# tinySensor.net
KiCad netlist of a schematic drawn in EAGLE
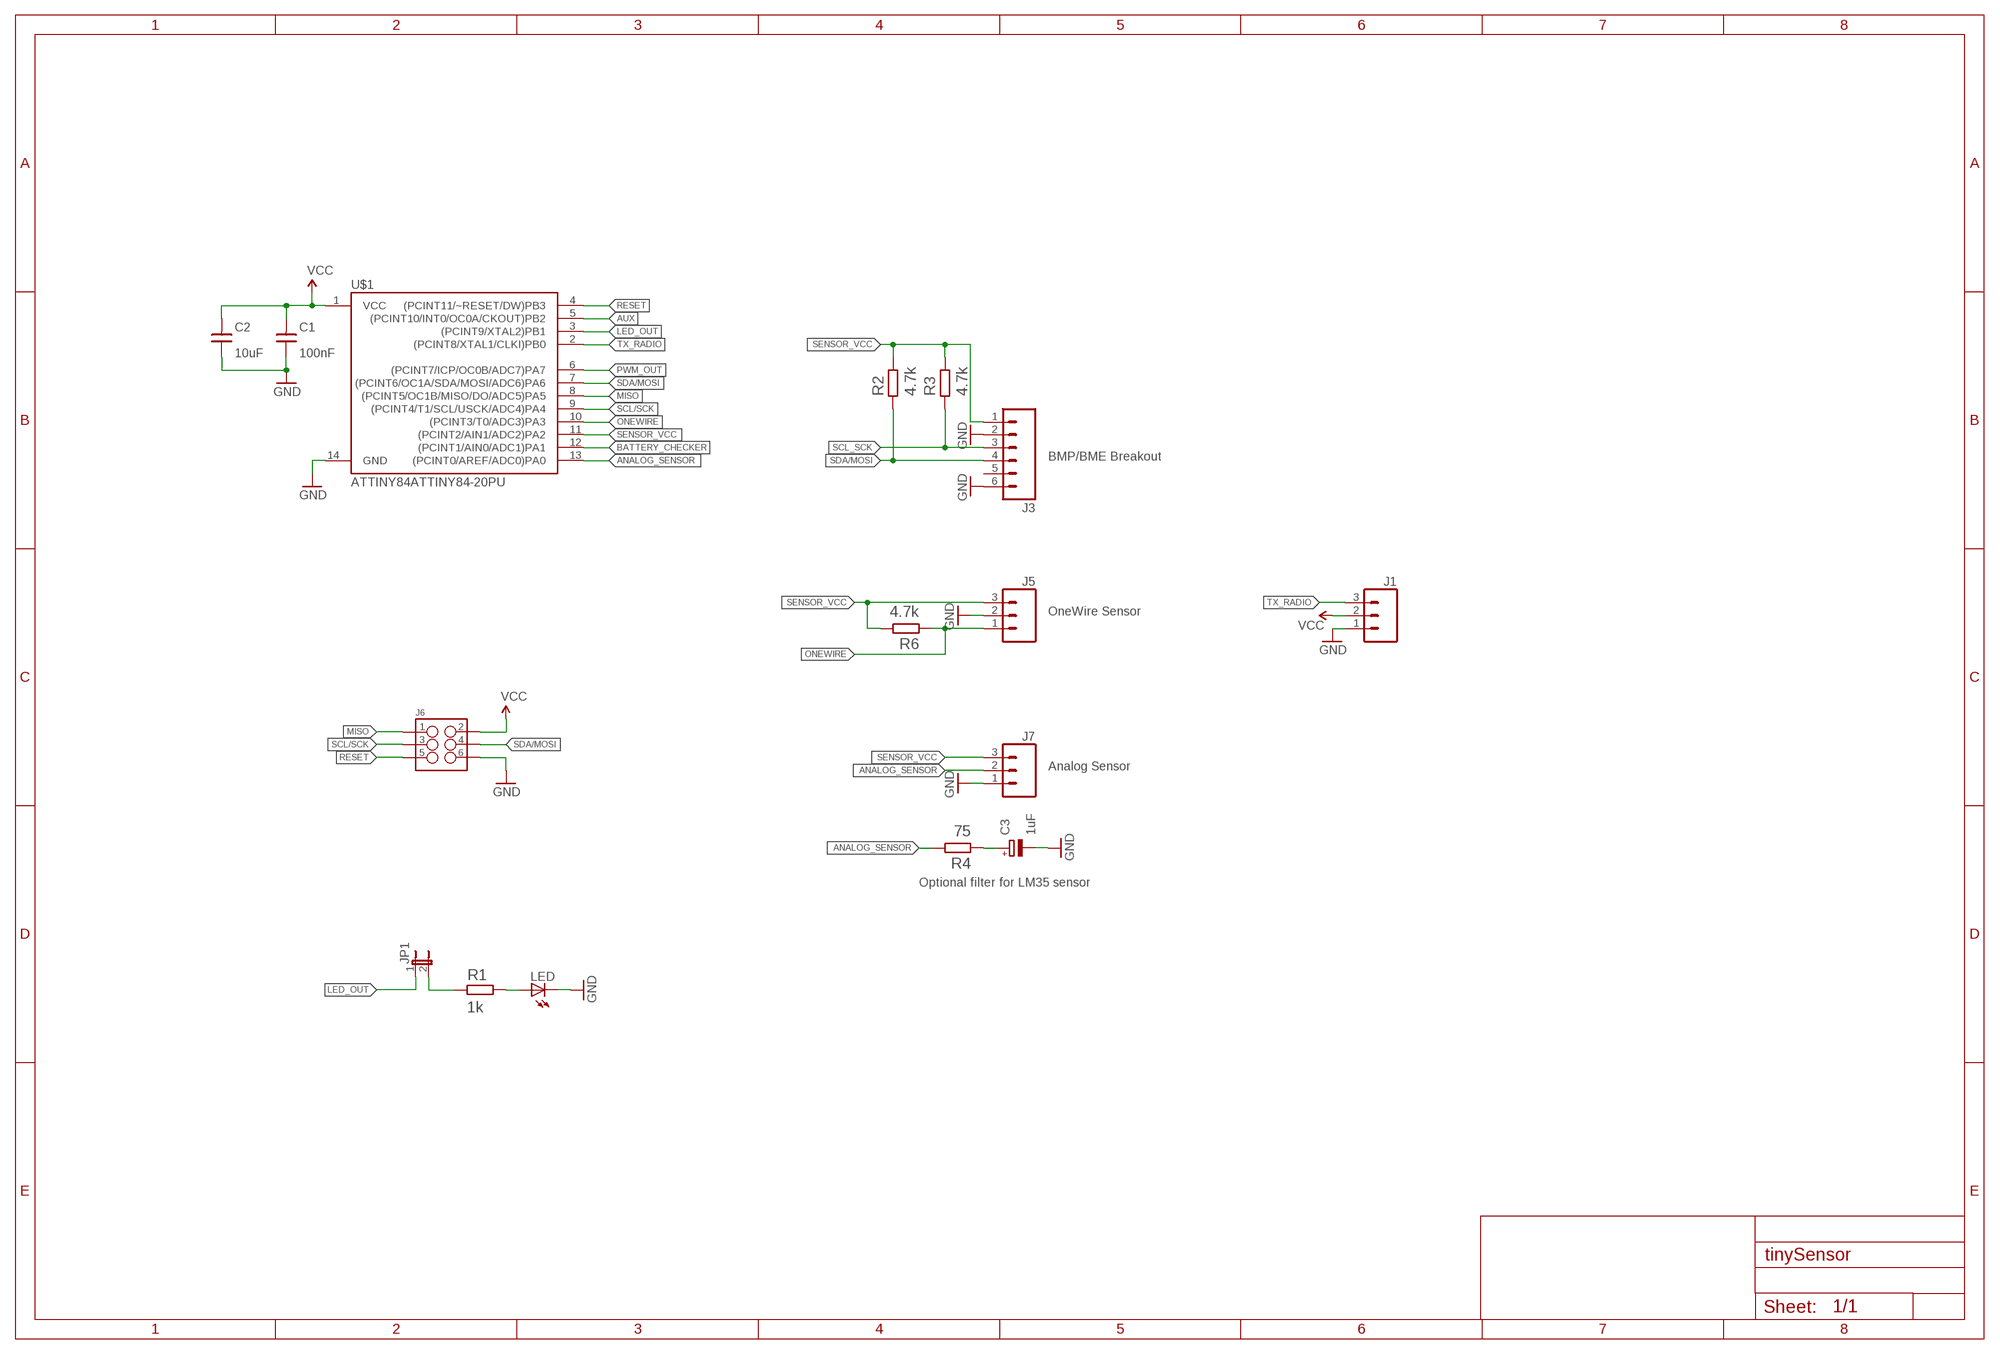
[diagram p0: schematic, sheet 1]

(export (version "E")
  (design (tool "Eeschema 10.0.6"))
  (components
    (comp (ref "C1")
      (value "100nF")
      (footprint "eagle-import:R0805")
      (libsource (lib "eagle-import") (part "C0805"))
    )
    (comp (ref "C2")
      (value "10uF")
      (footprint "eagle-import:R0805")
      (libsource (lib "eagle-import") (part "C0805"))
    )
    (comp (ref "C3")
      (value "1uF")
      (footprint "eagle-import:PANASONIC_C")
      (libsource (lib "eagle-import") (part "CPOL-EUC"))
    )
    (comp (ref "J1")
      (value "M03PTH")
      (footprint "eagle-import:1X03")
      (libsource (lib "eagle-import") (part "M03PTH"))
    )
    (comp (ref "J3")
      (value "M06SIP")
      (footprint "eagle-import:1X06")
      (libsource (lib "eagle-import") (part "M06SIP"))
    )
    (comp (ref "J5")
      (value "M03PTH")
      (footprint "eagle-import:1X03")
      (libsource (lib "eagle-import") (part "M03PTH"))
    )
    (comp (ref "J6")
      (value "M03X2SHROUD")
      (footprint "eagle-import:2X3-SHROUDED")
      (libsource (lib "eagle-import") (part "M03X2SHROUD"))
    )
    (comp (ref "J7")
      (value "M03PTH")
      (footprint "eagle-import:1X03")
      (libsource (lib "eagle-import") (part "M03PTH"))
    )
    (comp (ref "JP1")
      (value "JUMPER-2PTH")
      (footprint "eagle-import:1X02")
      (libsource (lib "eagle-import") (part "JUMPER-2PTH"))
    )
    (comp (ref "LED")
      (value "LED3MM")
      (footprint "eagle-import:LED3MM")
      (libsource (lib "eagle-import") (part "LED3MM"))
    )
    (comp (ref "R1")
      (value "1k")
      (footprint "eagle-import:R0805")
      (libsource (lib "eagle-import") (part "R0805"))
    )
    (comp (ref "R2")
      (value "4.7k")
      (footprint "eagle-import:R0805")
      (libsource (lib "eagle-import") (part "R0805"))
    )
    (comp (ref "R3")
      (value "4.7k")
      (footprint "eagle-import:R0805")
      (libsource (lib "eagle-import") (part "R0805"))
    )
    (comp (ref "R4")
      (value "75")
      (footprint "eagle-import:R0805")
      (libsource (lib "eagle-import") (part "R0805"))
    )
    (comp (ref "R6")
      (value "4.7k")
      (footprint "eagle-import:R0805")
      (libsource (lib "eagle-import") (part "R0805"))
    )
    (comp (ref "U$1")
      (value "ATTINY84ATTINY84-20PU")
      (footprint "eagle-import:DIL14")
      (libsource (lib "eagle-import") (part "ATTINY84ATTINY84-20PU"))
    )
  )
  (nets
    (net (code "1") (name "ANALOG_SENSOR") (class "Default")
      (node (ref "J7") (pin "2") (pinfunction "2_2") (pintype "passive"))
      (node (ref "R4") (pin "2") (pinfunction "2_2") (pintype "bidirectional"))
      (node (ref "U$1") (pin "13") (pinfunction "(PCINT0/AREF/ADC0)PA0_13") (pintype "bidirectional"))
    )
    (net (code "2") (name "AUX") (class "Default")
      (node (ref "U$1") (pin "5") (pinfunction "(PCINT10/INT0/OC0A/CKOUT)PB2_5") (pintype "bidirectional"))
    )
    (net (code "3") (name "BATTERY_CHECKER") (class "Default")
      (node (ref "U$1") (pin "12") (pinfunction "(PCINT1/AIN0/ADC1)PA1_12") (pintype "bidirectional"))
    )
    (net (code "4") (name "GND") (class "Default")
      (node (ref "C1") (pin "1") (pinfunction "1_1") (pintype "bidirectional"))
      (node (ref "C2") (pin "1") (pinfunction "1_1") (pintype "bidirectional"))
      (node (ref "C3") (pin "-") (pinfunction "-_-") (pintype "passive"))
      (node (ref "J1") (pin "1") (pinfunction "1_1") (pintype "passive"))
      (node (ref "J3") (pin "2") (pinfunction "2_2") (pintype "passive"))
      (node (ref "J3") (pin "6") (pinfunction "6_6") (pintype "passive"))
      (node (ref "J5") (pin "2") (pinfunction "2_2") (pintype "passive"))
      (node (ref "J6") (pin "6") (pinfunction "6_6") (pintype "bidirectional"))
      (node (ref "J7") (pin "1") (pinfunction "1_1") (pintype "passive"))
      (node (ref "LED") (pin "K") (pinfunction "C_K") (pintype "passive"))
      (node (ref "U$1") (pin "14") (pinfunction "GND_14") (pintype "bidirectional"))
    )
    (net (code "5") (name "LED_OUT") (class "Default")
      (node (ref "JP1") (pin "1") (pinfunction "1_1") (pintype "passive"))
      (node (ref "U$1") (pin "3") (pinfunction "(PCINT9/XTAL2)PB1_3") (pintype "bidirectional"))
    )
    (net (code "6") (name "MISO") (class "Default")
      (node (ref "J6") (pin "1") (pinfunction "1_1") (pintype "bidirectional"))
      (node (ref "U$1") (pin "8") (pinfunction "(PCINT5/OC1B/MISO/DO/ADC5)PA5_8") (pintype "bidirectional"))
    )
    (net (code "7") (name "Net-(C3-Pad+)") (class "Default")
      (node (ref "C3") (pin "+") (pinfunction "+_+") (pintype "passive"))
      (node (ref "R4") (pin "1") (pinfunction "1_1") (pintype "bidirectional"))
    )
    (net (code "8") (name "Net-(JP1-Pad2)") (class "Default")
      (node (ref "JP1") (pin "2") (pinfunction "2_2") (pintype "passive"))
      (node (ref "R1") (pin "1") (pinfunction "1_1") (pintype "bidirectional"))
    )
    (net (code "9") (name "Net-(LED-PadA)") (class "Default")
      (node (ref "LED") (pin "A") (pinfunction "A_A") (pintype "passive"))
      (node (ref "R1") (pin "2") (pinfunction "2_2") (pintype "bidirectional"))
    )
    (net (code "10") (name "ONEWIRE") (class "Default")
      (node (ref "J5") (pin "1") (pinfunction "1_1") (pintype "passive"))
      (node (ref "R6") (pin "1") (pinfunction "1_1") (pintype "bidirectional"))
      (node (ref "U$1") (pin "10") (pinfunction "(PCINT3/T0/ADC3)PA3_10") (pintype "bidirectional"))
    )
    (net (code "11") (name "PWM_OUT") (class "Default")
      (node (ref "U$1") (pin "6") (pinfunction "(PCINT7/ICP/OC0B/ADC7)PA7_6") (pintype "bidirectional"))
    )
    (net (code "12") (name "RESET") (class "Default")
      (node (ref "J6") (pin "5") (pinfunction "5_5") (pintype "bidirectional"))
      (node (ref "U$1") (pin "4") (pinfunction "(PCINT11/~{RESET/DW})PB3_4") (pintype "bidirectional"))
    )
    (net (code "13") (name "SCL_SCK") (class "Default")
      (node (ref "J3") (pin "3") (pinfunction "3_3") (pintype "passive"))
      (node (ref "R3") (pin "1") (pinfunction "1_1") (pintype "bidirectional"))
    )
    (net (code "14") (name "SCL{slash}SCK") (class "Default")
      (node (ref "J6") (pin "3") (pinfunction "3_3") (pintype "bidirectional"))
      (node (ref "U$1") (pin "9") (pinfunction "(PCINT4/T1/SCL/USCK/ADC4)PA4_9") (pintype "bidirectional"))
    )
    (net (code "15") (name "SDA{slash}MOSI") (class "Default")
      (node (ref "J3") (pin "4") (pinfunction "4_4") (pintype "passive"))
      (node (ref "J6") (pin "4") (pinfunction "4_4") (pintype "bidirectional"))
      (node (ref "R2") (pin "1") (pinfunction "1_1") (pintype "bidirectional"))
      (node (ref "U$1") (pin "7") (pinfunction "(PCINT6/OC1A/SDA/MOSI/ADC6)PA6_7") (pintype "bidirectional"))
    )
    (net (code "16") (name "SENSOR_VCC") (class "Default")
      (node (ref "J3") (pin "1") (pinfunction "1_1") (pintype "passive"))
      (node (ref "J5") (pin "3") (pinfunction "3_3") (pintype "passive"))
      (node (ref "J7") (pin "3") (pinfunction "3_3") (pintype "passive"))
      (node (ref "R2") (pin "2") (pinfunction "2_2") (pintype "bidirectional"))
      (node (ref "R3") (pin "2") (pinfunction "2_2") (pintype "bidirectional"))
      (node (ref "R6") (pin "2") (pinfunction "2_2") (pintype "bidirectional"))
      (node (ref "U$1") (pin "11") (pinfunction "(PCINT2/AIN1/ADC2)PA2_11") (pintype "bidirectional"))
    )
    (net (code "17") (name "TX_RADIO") (class "Default")
      (node (ref "J1") (pin "3") (pinfunction "3_3") (pintype "passive"))
      (node (ref "U$1") (pin "2") (pinfunction "(PCINT8/XTAL1/CLKI)PB0_2") (pintype "bidirectional"))
    )
    (net (code "18") (name "VCC") (class "Default")
      (node (ref "C1") (pin "2") (pinfunction "2_2") (pintype "bidirectional"))
      (node (ref "C2") (pin "2") (pinfunction "2_2") (pintype "bidirectional"))
      (node (ref "J1") (pin "2") (pinfunction "2_2") (pintype "passive"))
      (node (ref "J6") (pin "2") (pinfunction "2_2") (pintype "bidirectional"))
      (node (ref "U$1") (pin "1") (pinfunction "VCC_1") (pintype "bidirectional"))
    )
    (net (code "19") (name "unconnected-(J3-Pad5)") (class "Default")
      (node (ref "J3") (pin "5") (pinfunction "5_5") (pintype "passive"))
    )
  )
)
